# FT230X-Breakout-v10.net
KiCad netlist of a schematic drawn in EAGLE
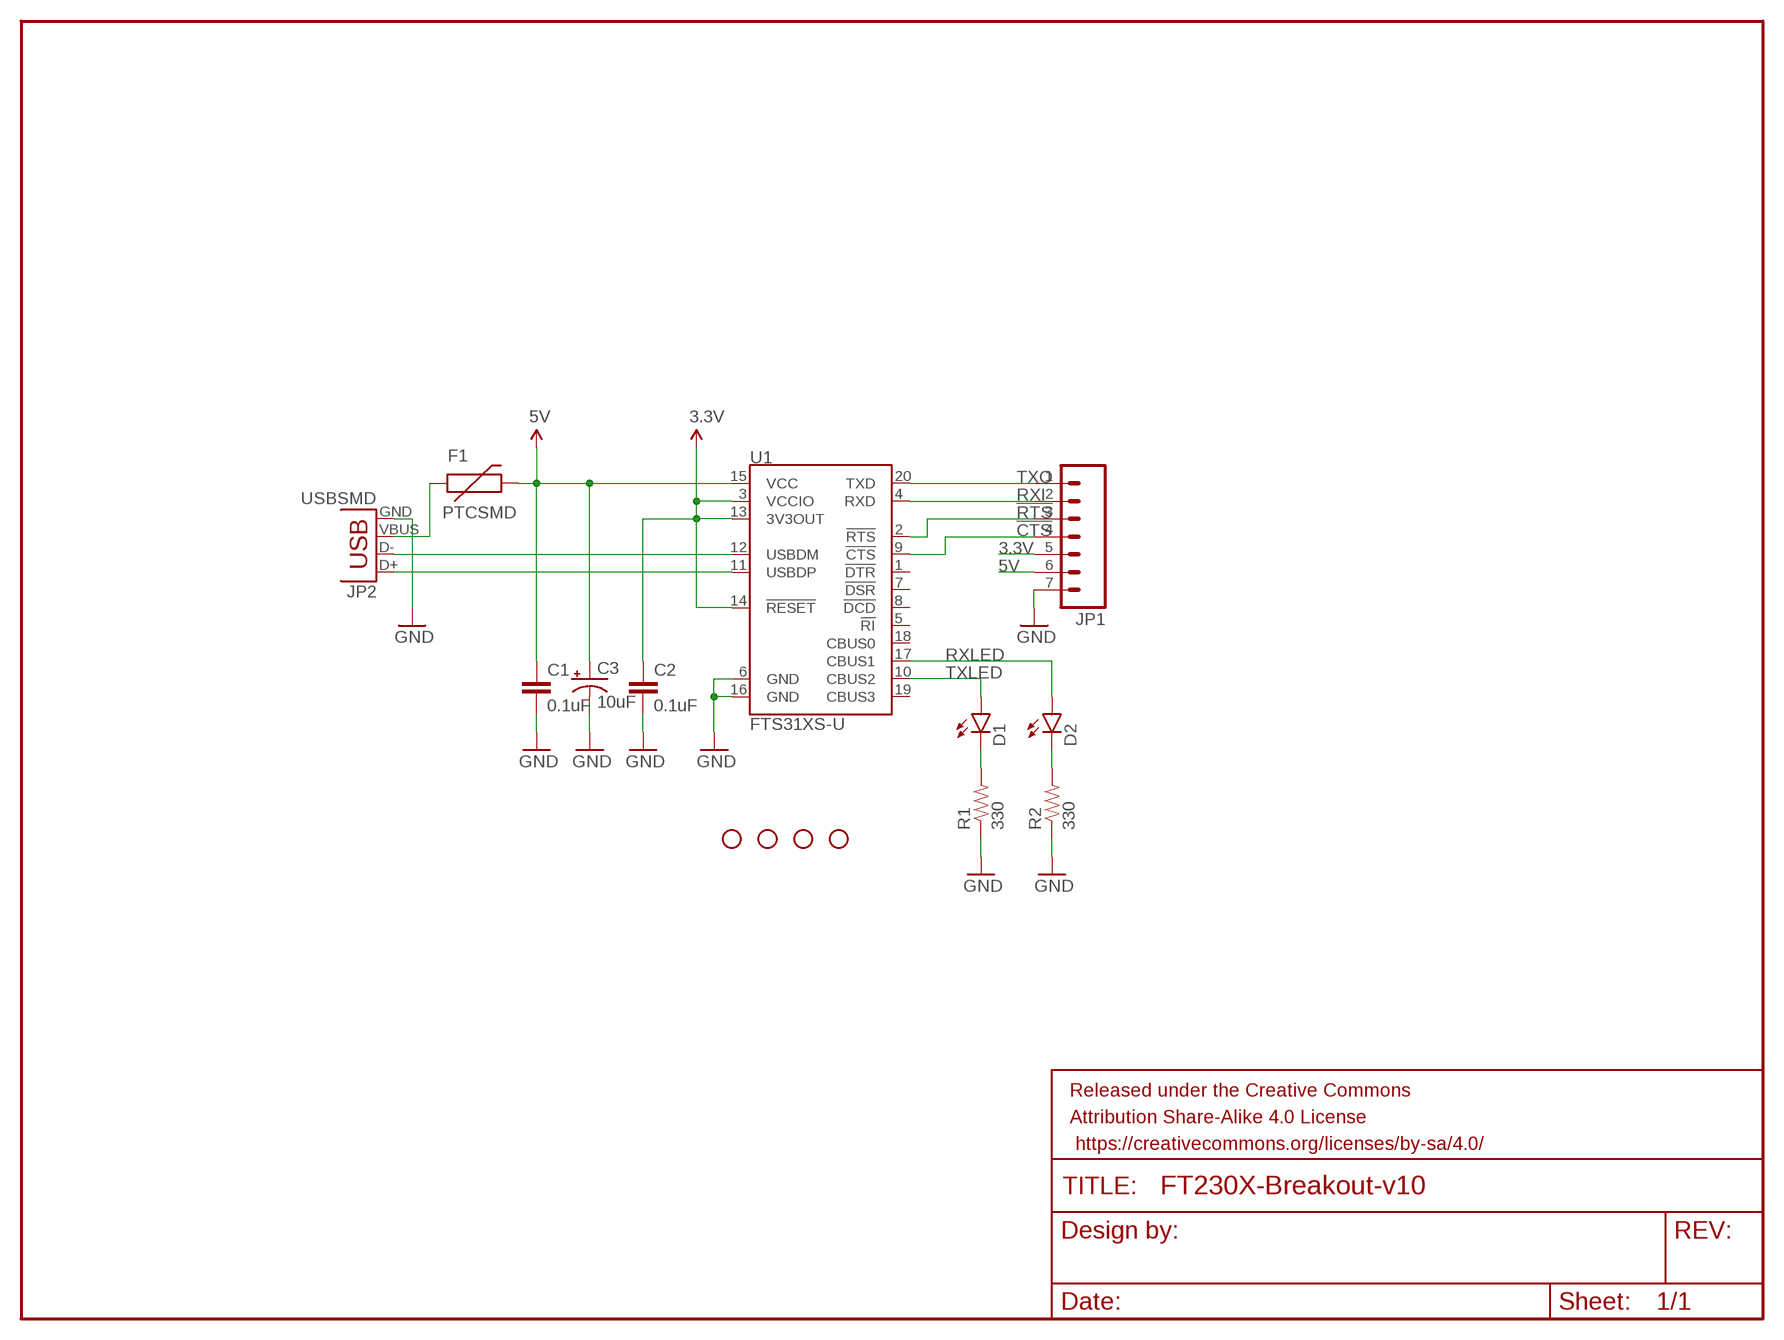
[diagram p0: schematic, sheet 1]

(export (version "E")
  (design (tool "Eeschema 10.0.6"))
  (components
    (comp (ref "C1")
      (value "0.1uF")
      (footprint "eagle-import:0603-CAP")
      (libsource (lib "eagle-import") (part "CAP0603-CAP"))
    )
    (comp (ref "C2")
      (value "0.1uF")
      (footprint "eagle-import:0603-CAP")
      (libsource (lib "eagle-import") (part "CAP0603-CAP"))
    )
    (comp (ref "C3")
      (value "10uF")
      (footprint "eagle-import:EIA3216-KIT")
      (libsource (lib "eagle-import") (part "CAP_POL1206-KIT"))
    )
    (comp (ref "D1")
      (value "LED0603")
      (footprint "eagle-import:LED-0603")
      (libsource (lib "eagle-import") (part "LED0603"))
    )
    (comp (ref "D2")
      (value "LED0603")
      (footprint "eagle-import:LED-0603")
      (libsource (lib "eagle-import") (part "LED0603"))
    )
    (comp (ref "F1")
      (value "PTCSMD")
      (footprint "eagle-import:PTC-1206")
      (libsource (lib "eagle-import") (part "PTCSMD"))
    )
    (comp (ref "FRAME1")
      (value "FRAME-LETTER")
      (footprint "eagle-import:CREATIVE_COMMONS")
      (libsource (lib "eagle-import") (part "FRAME-LETTER"))
    )
    (comp (ref "JP1")
      (value "M07")
      (footprint "eagle-import:1X07")
      (libsource (lib "eagle-import") (part "M07"))
    )
    (comp (ref "JP2")
      (value "USBSMD")
      (footprint "eagle-import:USB-MINIB")
      (libsource (lib "eagle-import") (part "USBSMD"))
    )
    (comp (ref "R1")
      (value "330")
      (footprint "eagle-import:0603-RES")
      (libsource (lib "eagle-import") (part "RESISTOR0603-RES"))
    )
    (comp (ref "R2")
      (value "330")
      (footprint "eagle-import:0603-RES")
      (libsource (lib "eagle-import") (part "RESISTOR0603-RES"))
    )
    (comp (ref "STANDOFF1")
      (value "STAND-OFF")
      (footprint "eagle-import:STAND-OFF")
      (libsource (lib "eagle-import") (part "STAND-OFF"))
    )
    (comp (ref "STANDOFF2")
      (value "STAND-OFF")
      (footprint "eagle-import:STAND-OFF")
      (libsource (lib "eagle-import") (part "STAND-OFF"))
    )
    (comp (ref "STANDOFF3")
      (value "STAND-OFF")
      (footprint "eagle-import:STAND-OFF")
      (libsource (lib "eagle-import") (part "STAND-OFF"))
    )
    (comp (ref "STANDOFF4")
      (value "STAND-OFF")
      (footprint "eagle-import:STAND-OFF")
      (libsource (lib "eagle-import") (part "STAND-OFF"))
    )
    (comp (ref "U1")
      (value "FTS31XS-U")
      (footprint "eagle-import:SSOP20_L")
      (libsource (lib "eagle-import") (part "FT231XS"))
    )
  )
  (nets
    (net (code "1") (name "/RXI") (class "Default")
      (node (ref "JP1") (pin "2") (pinfunction "2_2") (pintype "passive"))
      (node (ref "U1") (pin "4") (pinfunction "RXD_4") (pintype "bidirectional"))
    )
    (net (code "2") (name "/RXLED") (class "Default")
      (node (ref "D2") (pin "A") (pinfunction "A_A") (pintype "passive"))
      (node (ref "U1") (pin "17") (pinfunction "CBUS1_17") (pintype "bidirectional"))
    )
    (net (code "3") (name "/TXLED") (class "Default")
      (node (ref "D1") (pin "A") (pinfunction "A_A") (pintype "passive"))
      (node (ref "U1") (pin "10") (pinfunction "CBUS2_10") (pintype "bidirectional"))
    )
    (net (code "4") (name "/TXO") (class "Default")
      (node (ref "JP1") (pin "1") (pinfunction "1_1") (pintype "passive"))
      (node (ref "U1") (pin "20") (pinfunction "TXD_20") (pintype "bidirectional"))
    )
    (net (code "5") (name "/~{CTS}") (class "Default")
      (node (ref "JP1") (pin "4") (pinfunction "4_4") (pintype "passive"))
      (node (ref "U1") (pin "9") (pinfunction "~{CTS}_9") (pintype "bidirectional"))
    )
    (net (code "6") (name "/~{RTS}") (class "Default")
      (node (ref "JP1") (pin "3") (pinfunction "3_3") (pintype "passive"))
      (node (ref "U1") (pin "2") (pinfunction "~{RTS}_2") (pintype "bidirectional"))
    )
    (net (code "7") (name "3.3V") (class "Default")
      (node (ref "C2") (pin "1") (pinfunction "1_1") (pintype "passive"))
      (node (ref "JP1") (pin "5") (pinfunction "5_5") (pintype "passive"))
      (node (ref "U1") (pin "13") (pinfunction "3V3OUT_13") (pintype "bidirectional"))
      (node (ref "U1") (pin "14") (pinfunction "~{RESET}_14") (pintype "bidirectional"))
      (node (ref "U1") (pin "3") (pinfunction "VCCIO_3") (pintype "bidirectional"))
    )
    (net (code "8") (name "5V") (class "Default")
      (node (ref "C1") (pin "1") (pinfunction "1_1") (pintype "passive"))
      (node (ref "C3") (pin "A") (pinfunction "+_A") (pintype "passive"))
      (node (ref "F1") (pin "2") (pinfunction "2_2") (pintype "bidirectional"))
      (node (ref "JP1") (pin "6") (pinfunction "6_6") (pintype "passive"))
      (node (ref "U1") (pin "15") (pinfunction "VCC_15") (pintype "bidirectional"))
    )
    (net (code "9") (name "GND") (class "Default")
      (node (ref "C1") (pin "2") (pinfunction "2_2") (pintype "passive"))
      (node (ref "C2") (pin "2") (pinfunction "2_2") (pintype "passive"))
      (node (ref "C3") (pin "C") (pinfunction "-_C") (pintype "passive"))
      (node (ref "JP1") (pin "7") (pinfunction "7_7") (pintype "passive"))
      (node (ref "JP2") (pin "GND") (pinfunction "GND_GND") (pintype "bidirectional"))
      (node (ref "R1") (pin "1") (pinfunction "1_1") (pintype "passive"))
      (node (ref "R2") (pin "1") (pinfunction "1_1") (pintype "passive"))
      (node (ref "U1") (pin "16") (pinfunction "GND_16") (pintype "bidirectional"))
      (node (ref "U1") (pin "6") (pinfunction "GND_6") (pintype "bidirectional"))
    )
    (net (code "10") (name "Net-(D1-PadC)") (class "Default")
      (node (ref "D1") (pin "C") (pinfunction "C_C") (pintype "passive"))
      (node (ref "R1") (pin "2") (pinfunction "2_2") (pintype "passive"))
    )
    (net (code "11") (name "Net-(D2-PadC)") (class "Default")
      (node (ref "D2") (pin "C") (pinfunction "C_C") (pintype "passive"))
      (node (ref "R2") (pin "2") (pinfunction "2_2") (pintype "passive"))
    )
    (net (code "12") (name "Net-(F1-Pad1)") (class "Default")
      (node (ref "F1") (pin "1") (pinfunction "1_1") (pintype "bidirectional"))
      (node (ref "JP2") (pin "VBUS") (pinfunction "VBUS_VBUS") (pintype "bidirectional"))
    )
    (net (code "13") (name "Net-(U1-USBDM)") (class "Default")
      (node (ref "JP2") (pin "D-") (pinfunction "D-_D-") (pintype "bidirectional"))
      (node (ref "U1") (pin "12") (pinfunction "USBDM_12") (pintype "bidirectional"))
    )
    (net (code "14") (name "Net-(U1-USBDP)") (class "Default")
      (node (ref "JP2") (pin "D+") (pinfunction "D+_D+") (pintype "bidirectional"))
      (node (ref "U1") (pin "11") (pinfunction "USBDP_11") (pintype "bidirectional"))
    )
    (net (code "15") (name "unconnected-(U1-CBUS0-Pad18)") (class "Default")
      (node (ref "U1") (pin "18") (pinfunction "CBUS0_18") (pintype "bidirectional"))
    )
    (net (code "16") (name "unconnected-(U1-CBUS3-Pad19)") (class "Default")
      (node (ref "U1") (pin "19") (pinfunction "CBUS3_19") (pintype "bidirectional"))
    )
    (net (code "17") (name "unconnected-(U1-~{DCD}-Pad8)") (class "Default")
      (node (ref "U1") (pin "8") (pinfunction "~{DCD}_8") (pintype "bidirectional"))
    )
    (net (code "18") (name "unconnected-(U1-~{DSR}-Pad7)") (class "Default")
      (node (ref "U1") (pin "7") (pinfunction "~{DSR}_7") (pintype "bidirectional"))
    )
    (net (code "19") (name "unconnected-(U1-~{DTR}-Pad1)") (class "Default")
      (node (ref "U1") (pin "1") (pinfunction "~{DTR}_1") (pintype "bidirectional"))
    )
    (net (code "20") (name "unconnected-(U1-~{RI}-Pad5)") (class "Default")
      (node (ref "U1") (pin "5") (pinfunction "~{RI}_5") (pintype "bidirectional"))
    )
  )
)
